# Gastroscopy-Tool-Interface_3V3_Domain.net
KiCad netlist of a schematic drawn in Altium Designer
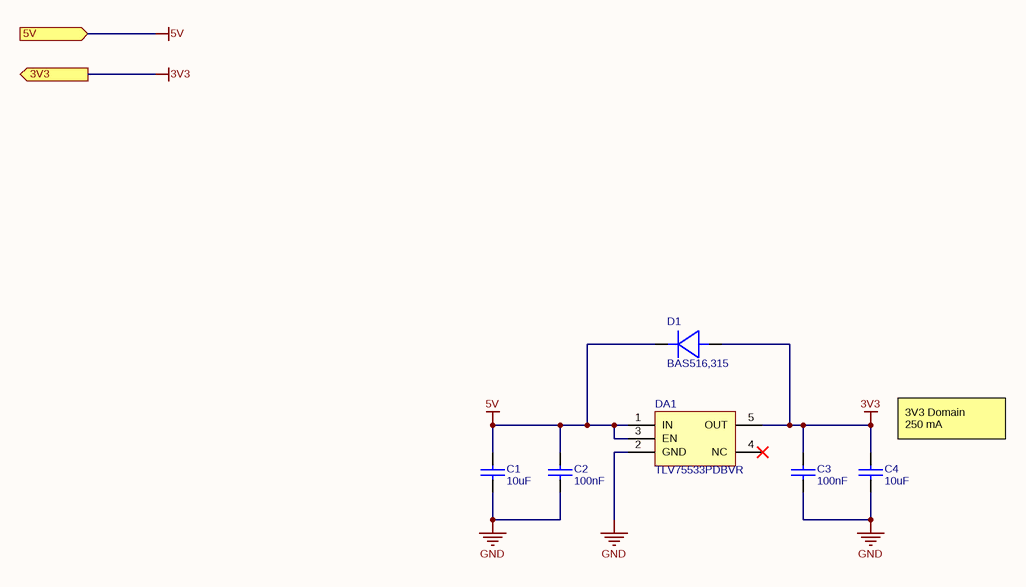
[diagram p0: Gastroscopy-Tool-Interface_3V3_Domain.SchDoc]

(export (version "E")
  (design (tool "Eeschema 10.0.6"))
  (components
    (comp (ref "C1")
      (value "10uF")
      (footprint "CAP_0805")
      (description "CAP CER 10UF 16V X7R 0805")
      (fields
        (field (name "MANUFACTURER") "Samsung")
        (field (name "MANUFACTURER PART NUMBER") "CL21B106KOQNNNE")
      )
      (libsource (lib "Gastroscopy-Tool") (part "CL21B106KOQNNNE"))
    )
    (comp (ref "C2")
      (value "100nF")
      (footprint "CAP_0603")
      (description "CAP CER 0.1UF 50V X7R 0603")
      (fields (field (name "TOLERANCE") "10%"))
      (libsource (lib "Industrial-Controller") (part "CL10B104KB8NNNL"))
    )
    (comp (ref "C3")
      (value "100nF")
      (footprint "CAP_0603")
      (description "CAP CER 0.1UF 50V X7R 0603")
      (fields (field (name "TOLERANCE") "10%"))
      (libsource (lib "Industrial-Controller") (part "CL10B104KB8NNNL"))
    )
    (comp (ref "C4")
      (value "10uF")
      (footprint "CAP_0805")
      (description "CAP CER 10UF 16V X7R 0805")
      (fields
        (field (name "MANUFACTURER") "Samsung")
        (field (name "MANUFACTURER PART NUMBER") "CL21B106KOQNNNE")
      )
      (libsource (lib "Gastroscopy-Tool") (part "CL21B106KOQNNNE"))
    )
    (comp (ref "D1")
      (value "BAS516,315")
      (footprint "SOD-523")
      (description "DIODE GEN PURP 100V 250MA SOD523")
      (libsource (lib "Gastroscopy-Tool") (part "BAS516,315"))
    )
    (comp (ref "DA1")
      (value "TLV75533PDBVR")
      (footprint "SOT-23-5")
      (description "IC REG LINEAR 3.3V 500MA SOT23-5")
      (libsource (lib "Industrial-Controller") (part "TLV75533PDBVR"))
    )
  )
  (nets
    (net (code "1") (name "3V3") (class "Default")
      (node (ref "C3") (pin "1") (pinfunction "1_1") (pintype "passive"))
      (node (ref "C4") (pin "2") (pinfunction "2_2") (pintype "passive"))
      (node (ref "D1") (pin "2") (pinfunction "A_2") (pintype "passive"))
      (node (ref "DA1") (pin "5") (pinfunction "OUT_5") (pintype "passive"))
    )
    (net (code "2") (name "5V") (class "Default")
      (node (ref "C1") (pin "2") (pinfunction "2_2") (pintype "passive"))
      (node (ref "C2") (pin "1") (pinfunction "1_1") (pintype "passive"))
      (node (ref "D1") (pin "1") (pinfunction "C_1") (pintype "passive"))
      (node (ref "DA1") (pin "1") (pinfunction "IN_1") (pintype "passive"))
      (node (ref "DA1") (pin "3") (pinfunction "EN_3") (pintype "passive"))
    )
    (net (code "3") (name "GND") (class "Default")
      (node (ref "C1") (pin "1") (pinfunction "1_1") (pintype "passive"))
      (node (ref "C2") (pin "2") (pinfunction "2_2") (pintype "passive"))
      (node (ref "C3") (pin "2") (pinfunction "2_2") (pintype "passive"))
      (node (ref "C4") (pin "1") (pinfunction "1_1") (pintype "passive"))
      (node (ref "DA1") (pin "2") (pinfunction "GND_2") (pintype "power_in"))
    )
    (net (code "4") (name "unconnected-(DA1-NC-Pad4)") (class "Default")
      (node (ref "DA1") (pin "4") (pinfunction "NC_4") (pintype "power_in+no_connect"))
    )
  )
)
